# SATA.net
KiCad netlist of a schematic drawn in Altium Designer
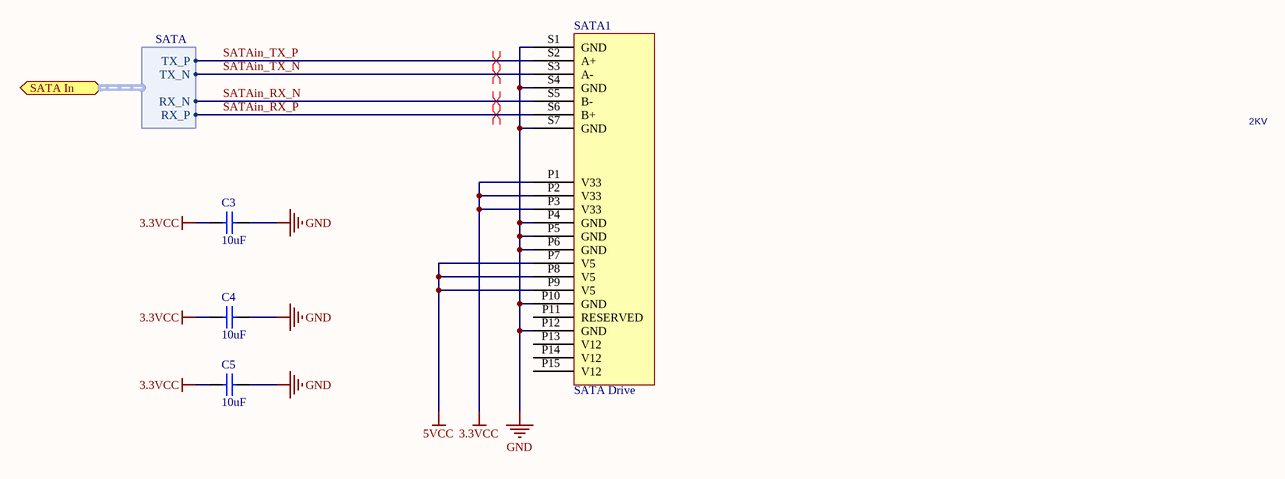
[diagram p0: SATA.SchDoc]

(export (version "E")
  (design (tool "Eeschema 10.0.6"))
  (components
    (comp (ref "C3")
      (value "10uF")
      (footprint "1210 (3225) Capacitor")
      (description "Capacitor")
      (fields (field (name "DIGIKEY PART NUMBER") "Digi-Key"))
      (libsource (lib "PassiveComponents") (part "Capacitor (non-polarized)"))
    )
    (comp (ref "C4")
      (value "10uF")
      (footprint "1210 (3225) Capacitor")
      (description "Capacitor")
      (fields (field (name "DIGIKEY PART NUMBER") "Digi-Key"))
      (libsource (lib "PassiveComponents") (part "Capacitor (non-polarized)"))
    )
    (comp (ref "C5")
      (value "10uF")
      (footprint "1210 (3225) Capacitor")
      (description "Capacitor")
      (fields (field (name "DIGIKEY PART NUMBER") "Digi-Key"))
      (libsource (lib "PassiveComponents") (part "Capacitor (non-polarized)"))
    )
    (comp (ref "SATA1")
      (value "SATA Drive")
      (footprint "SATAConnectors:SandiskMini")
      (description "SATA HDD, FCI Part# 10029364")
      (libsource (lib "SATAConnectors") (part "SATA Drive"))
    )
  )
  (nets
    (net (code "2") (name "/SATAin_RX_N") (class "Default")
      (node (ref "SATA1") (pin "S5") (pinfunction "B-_S5") (pintype "passive"))
    )
    (net (code "3") (name "/SATAin_RX_P") (class "Default")
      (node (ref "SATA1") (pin "S6") (pinfunction "B+_S6") (pintype "passive"))
    )
    (net (code "4") (name "/SATAin_TX_N") (class "Default")
      (node (ref "SATA1") (pin "S3") (pinfunction "A-_S3") (pintype "passive"))
    )
    (net (code "5") (name "/SATAin_TX_P") (class "Default")
      (node (ref "SATA1") (pin "S2") (pinfunction "A+_S2") (pintype "passive"))
    )
    (net (code "7") (name "3.3VCC") (class "Default")
      (node (ref "C3") (pin "2") (pinfunction "2_2") (pintype "passive"))
      (node (ref "C4") (pin "2") (pinfunction "2_2") (pintype "passive"))
      (node (ref "C5") (pin "2") (pinfunction "2_2") (pintype "passive"))
      (node (ref "SATA1") (pin "P1") (pinfunction "V33_P1") (pintype "passive"))
      (node (ref "SATA1") (pin "P2") (pinfunction "V33_P2") (pintype "passive"))
      (node (ref "SATA1") (pin "P3") (pinfunction "V33_P3") (pintype "passive"))
    )
    (net (code "8") (name "5VCC") (class "Default")
      (node (ref "SATA1") (pin "P7") (pinfunction "V5_P7") (pintype "passive"))
      (node (ref "SATA1") (pin "P8") (pinfunction "V5_P8") (pintype "passive"))
      (node (ref "SATA1") (pin "P9") (pinfunction "V5_P9") (pintype "passive"))
    )
    (net (code "9") (name "GND") (class "Default")
      (node (ref "C3") (pin "1") (pinfunction "1_1") (pintype "passive"))
      (node (ref "C4") (pin "1") (pinfunction "1_1") (pintype "passive"))
      (node (ref "C5") (pin "1") (pinfunction "1_1") (pintype "passive"))
      (node (ref "SATA1") (pin "P10") (pinfunction "GND_P10") (pintype "passive"))
      (node (ref "SATA1") (pin "P12") (pinfunction "GND_P12") (pintype "passive"))
      (node (ref "SATA1") (pin "P4") (pinfunction "GND_P4") (pintype "passive"))
      (node (ref "SATA1") (pin "P5") (pinfunction "GND_P5") (pintype "passive"))
      (node (ref "SATA1") (pin "P6") (pinfunction "GND_P6") (pintype "passive"))
      (node (ref "SATA1") (pin "S1") (pinfunction "GND_S1") (pintype "passive"))
      (node (ref "SATA1") (pin "S4") (pinfunction "GND_S4") (pintype "passive"))
      (node (ref "SATA1") (pin "S7") (pinfunction "GND_S7") (pintype "passive"))
    )
    (net (code "10") (name "unconnected-(SATA1-RESERVED-PadP11)") (class "Default")
      (node (ref "SATA1") (pin "P11") (pinfunction "RESERVED_P11") (pintype "passive"))
    )
    (net (code "11") (name "unconnected-(SATA1-V12-PadP13)") (class "Default")
      (node (ref "SATA1") (pin "P13") (pinfunction "V12_P13") (pintype "passive"))
    )
    (net (code "12") (name "unconnected-(SATA1-V12-PadP14)") (class "Default")
      (node (ref "SATA1") (pin "P14") (pinfunction "V12_P14") (pintype "passive"))
    )
    (net (code "13") (name "unconnected-(SATA1-V12-PadP15)") (class "Default")
      (node (ref "SATA1") (pin "P15") (pinfunction "V12_P15") (pintype "passive"))
    )
  )
)
